# Top_Sensor_PCB_S201.net
KiCad netlist of a schematic drawn in Altium Designer
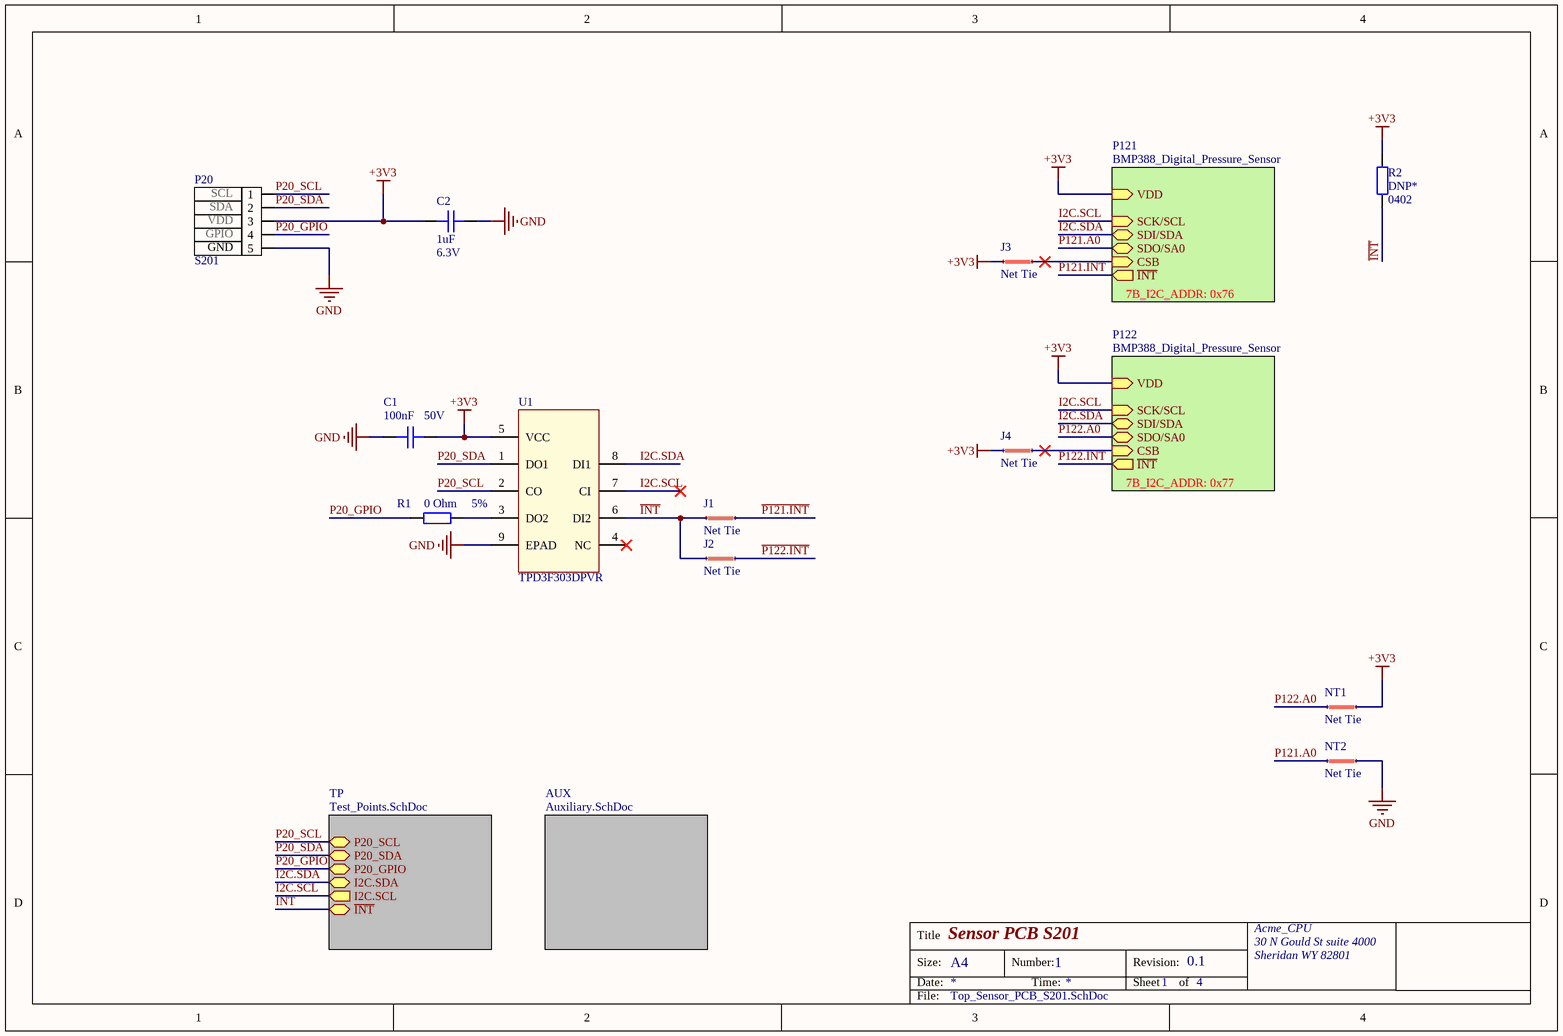
[diagram p0: Top_Sensor_PCB_S201.SchDoc]

(export (version "E")
  (design (tool "Eeschema 10.0.6"))
  (components
    (comp (ref "C1")
      (value "CAP CER 0.1UF 50V X7R 0402")
      (footprint "C0402")
      (description "0.1µF ±10% 50V Ceramic Capacitor X7R 0402 (1005 Metric)")
      (fields
        (field (name "MANUFACTURER") "TDK")
        (field (name "MANUFACTURER PART NUMBER") "CGA2B3X7R1H104K050BB")
        (field (name "CAPACITANCE") "100nF")
        (field (name "VOLTAGE") "50V")
      )
      (libsource (lib "capacitors_smd") (part "CAP CER 0.1UF 50V X7R 0402"))
    )
    (comp (ref "C2")
      (value "CAP CER 1UF 6.3V X5R 0402")
      (footprint "C0402")
      (description "1µF ±10% 6.3V Ceramic Capacitor X5R 0402 (1005 Metric)")
      (fields
        (field (name "MANUFACTURER") "Yageo")
        (field (name "MANUFACTURER PART NUMBER") "CC0402KRX5R5BB105")
        (field (name "CAPACITANCE") "1uF")
        (field (name "VOLTAGE RATING") "6.3V")
      )
      (libsource (lib "capacitors_smd") (part "CAP CER 1UF 6.3V X5R 0402"))
    )
    (comp (ref "J1")
      (value "Net Tie")
      (footprint "Net Tie 6x30mil")
      (libsource (lib "BLDC_Motor_Driver") (part "Net Tie Line"))
    )
    (comp (ref "J2")
      (value "Net Tie")
      (footprint "Net Tie 6x30mil")
      (libsource (lib "BLDC_Motor_Driver") (part "Net Tie Line"))
    )
    (comp (ref "J3")
      (value "Net Tie")
      (footprint "Net Tie 6x30mil")
      (libsource (lib "BLDC_Motor_Driver") (part "Net Tie Line"))
    )
    (comp (ref "J4")
      (value "Net Tie")
      (footprint "Net Tie 6x30mil")
      (libsource (lib "BLDC_Motor_Driver") (part "Net Tie Line"))
    )
    (comp (ref "NT1")
      (value "Net Tie")
      (footprint "Net Tie 6x30mil")
      (libsource (lib "BLDC_Motor_Driver") (part "Net Tie Line"))
    )
    (comp (ref "NT2")
      (value "Net Tie")
      (footprint "Net Tie 6x30mil")
      (libsource (lib "BLDC_Motor_Driver") (part "Net Tie Line"))
    )
    (comp (ref "P20")
      (value "S201")
      (footprint "5-PIN FPC BOARD EDGE CONNECTOR 0.5MM")
      (description "Connector Header Through Hole, Right Angle 5 position 0.059\" (1.50mm)")
      (fields
        (field (name "MANUFACTURER") "JST")
        (field (name "MANUFACTURER PART NUMBER") "S5B-ZR(LF)(SN)")
        (field (name "PIN_1") "SCL")
        (field (name "PIN_2") "SDA")
        (field (name "PIN_3") "VDD")
        (field (name "PIN_4") "GPIO")
        (field (name "PIN_5") "GND")
      )
      (libsource (lib "connectors_header") (part "CONN HEADER TH R/A 5POS 1.5MM"))
    )
    (comp (ref "R1")
      (value "RES SMD 0 OHM JUMPER 1/16W 0402")
      (footprint "R0402")
      (description "0 Ohms Jumper 0.063W, 1/16W Chip Resistor 0402 (1005 Metric) Moisture Resistant Thick Film")
      (fields
        (field (name "MANUFACTURER") "Yageo")
        (field (name "MANUFACTURER PART NUMBER") "RC0402JR-070RL")
        (field (name "TOLERANCE") "5%")
        (field (name "RESISTANCE") "0 Ohm")
      )
      (libsource (lib "resistors_smd") (part "RES SMD 0 OHM JUMPER 1/16W 0402"))
    )
    (comp (ref "R2")
      (value "DNP*")
      (footprint "R0402")
      (description "Placeholder for a 0402 resistor")
      (fields (field (name "CASE/PACKAGE") "0402"))
      (libsource (lib "resistors_smd") (part "RES SMD NO BOM 0402"))
    )
    (comp (ref "U1")
      (value "TPD3F303DPVR")
      (footprint "DPV8_1P7X0P4")
      (description "RC (Pi) EMI Filter 2nd Order Low Pass 3 Channel R = 47Ohms, 100Ohms, C = 20pF  8-UFDFN Exposed Pad")
      (fields (field (name "MANUFACTURER") "Texas Instruments"))
      (libsource (lib "diodes_tvs") (part "FILTER RC(PI) ESD SMD  8-UFDFN EP"))
    )
  )
  (nets
    (net (code "1") (name "+3V3") (class "Default")
      (node (ref "C1") (pin "1") (pinfunction "1_1") (pintype "passive"))
      (node (ref "C2") (pin "2") (pinfunction "2_2") (pintype "passive"))
      (node (ref "J3") (pin "1") (pintype "passive"))
      (node (ref "J4") (pin "1") (pintype "passive"))
      (node (ref "NT1") (pin "2") (pintype "passive"))
      (node (ref "P20") (pin "3") (pinfunction "3_3") (pintype "passive"))
      (node (ref "R2") (pin "2") (pinfunction "2_2") (pintype "passive"))
      (node (ref "U1") (pin "5") (pinfunction "VCC_5") (pintype "power_in"))
    )
    (net (code "2") (name "/CSB") (class "Default") (node (ref "J3") (pin "2") (pintype "passive")))
    (net (code "3") (name "/CSB_1") (class "Default") (node (ref "J4") (pin "2") (pintype "passive")))
    (net (code "4") (name "/I2C.SCL") (class "Default")
      (node (ref "U1") (pin "7") (pinfunction "CI_7") (pintype "passive+no_connect"))
    )
    (net (code "5") (name "/I2C.SDA") (class "Default")
      (node (ref "U1") (pin "8") (pinfunction "DI1_8") (pintype "passive"))
    )
    (net (code "6") (name "/INT") (class "Default")
      (node (ref "J1") (pin "1") (pintype "passive"))
      (node (ref "J2") (pin "1") (pintype "passive"))
      (node (ref "R2") (pin "1") (pinfunction "1_1") (pintype "passive"))
      (node (ref "U1") (pin "6") (pinfunction "DI2_6") (pintype "passive"))
    )
    (net (code "7") (name "/P20_GPIO") (class "Default")
      (node (ref "P20") (pin "4") (pinfunction "4_4") (pintype "passive"))
      (node (ref "R1") (pin "2") (pinfunction "2_2") (pintype "passive"))
    )
    (net (code "8") (name "/P20_SCL") (class "Default")
      (node (ref "P20") (pin "1") (pinfunction "1_1") (pintype "passive"))
      (node (ref "U1") (pin "2") (pinfunction "CO_2") (pintype "passive"))
    )
    (net (code "9") (name "/P20_SDA") (class "Default")
      (node (ref "P20") (pin "2") (pinfunction "2_2") (pintype "passive"))
      (node (ref "U1") (pin "1") (pinfunction "DO1_1") (pintype "passive"))
    )
    (net (code "10") (name "/P121.A0") (class "Default") (node (ref "NT2") (pin "1") (pintype "passive")))
    (net (code "11") (name "/P121.INT") (class "Default") (node (ref "J1") (pin "2") (pintype "passive")))
    (net (code "12") (name "/P122.A0") (class "Default") (node (ref "NT1") (pin "1") (pintype "passive")))
    (net (code "13") (name "/P122.INT") (class "Default") (node (ref "J2") (pin "2") (pintype "passive")))
    (net (code "14") (name "GND") (class "Default")
      (node (ref "C1") (pin "2") (pinfunction "2_2") (pintype "passive"))
      (node (ref "C2") (pin "1") (pinfunction "1_1") (pintype "passive"))
      (node (ref "NT2") (pin "2") (pintype "passive"))
      (node (ref "P20") (pin "5") (pinfunction "5_5") (pintype "passive"))
      (node (ref "U1") (pin "9") (pinfunction "EPAD_9") (pintype "passive"))
    )
    (net (code "15") (name "Net-(U1-DO2)") (class "Default")
      (node (ref "R1") (pin "1") (pinfunction "1_1") (pintype "passive"))
      (node (ref "U1") (pin "3") (pinfunction "DO2_3") (pintype "passive"))
    )
    (net (code "16") (name "unconnected-(U1-NC-Pad4)") (class "Default")
      (node (ref "U1") (pin "4") (pinfunction "NC_4") (pintype "passive+no_connect"))
    )
  )
)
